# Shield.net
KiCad netlist of a schematic drawn in EAGLE
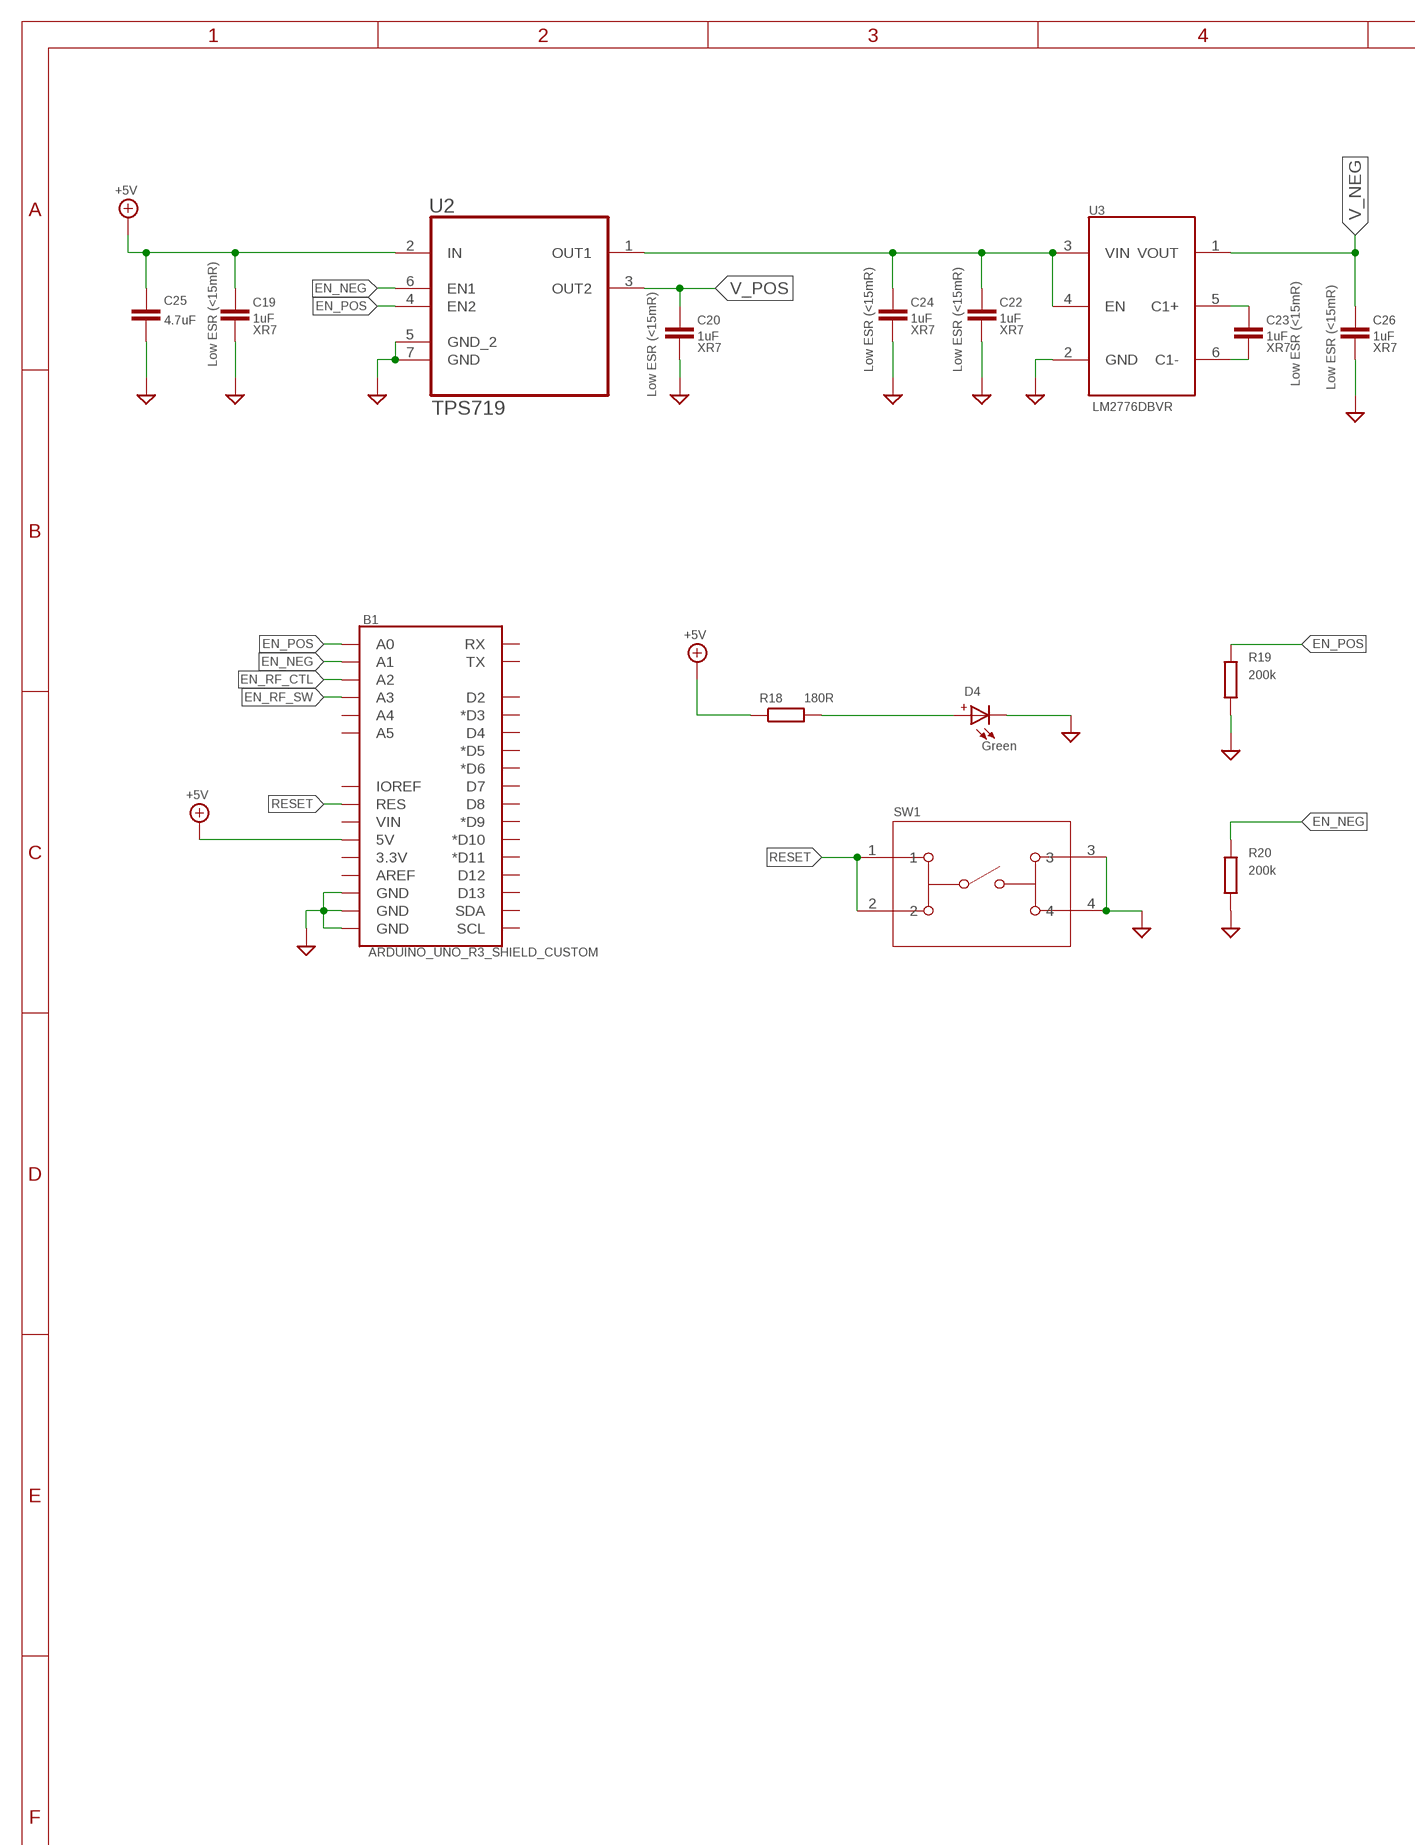
[diagram p0: schematic, sheet 1, part 1 of 2]
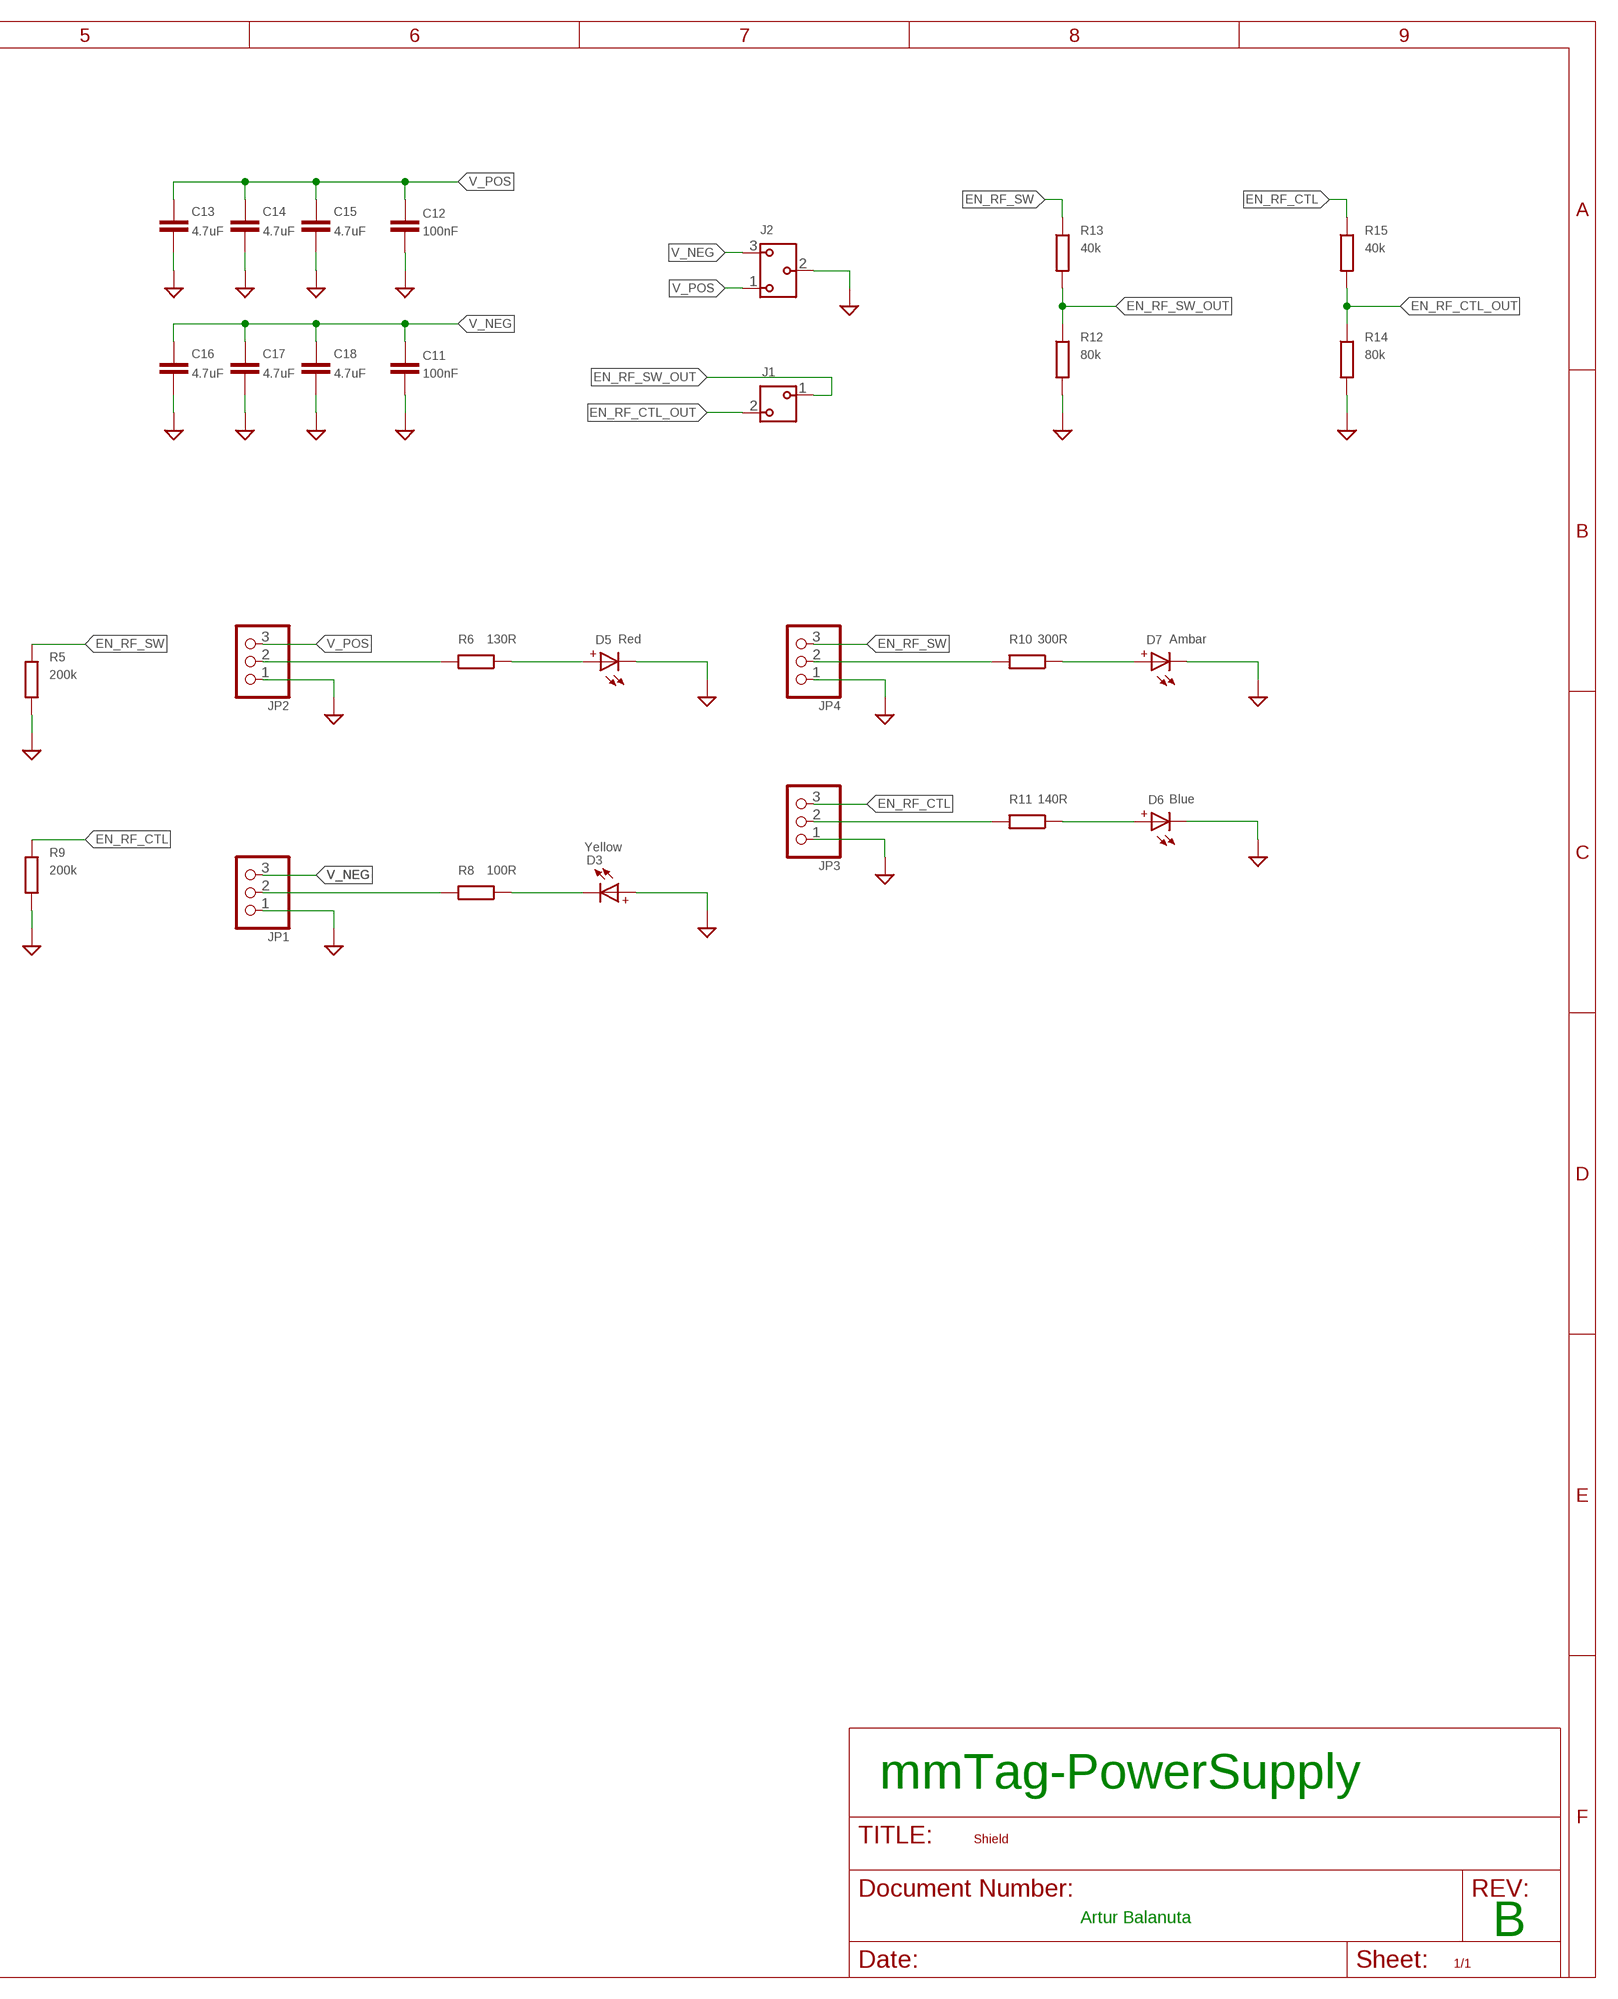
[diagram p1: schematic, sheet 1, part 2 of 2]

(export (version "E")
  (design (tool "Eeschema 10.0.6"))
  (components
    (comp (ref "B1")
      (value "ARDUINO_UNO_R3_SHIELD_CUSTOM")
      (footprint "eagle-import:UNO_R3_SHIELD_NO_PROG")
      (libsource (lib "eagle-import") (part "ARDUINO_UNO_R3_SHIELD_CUSTOM"))
    )
    (comp (ref "C11")
      (value "100nF")
      (footprint "eagle-import:C0603")
      (libsource (lib "eagle-import") (part "C-EUC0603"))
    )
    (comp (ref "C12")
      (value "100nF")
      (footprint "eagle-import:C0603")
      (libsource (lib "eagle-import") (part "C-EUC0603"))
    )
    (comp (ref "C13")
      (value "4.7uF")
      (footprint "eagle-import:C1206")
      (libsource (lib "eagle-import") (part "C-EUC1206"))
    )
    (comp (ref "C14")
      (value "4.7uF")
      (footprint "eagle-import:C1206")
      (libsource (lib "eagle-import") (part "C-EUC1206"))
    )
    (comp (ref "C15")
      (value "4.7uF")
      (footprint "eagle-import:C1206")
      (libsource (lib "eagle-import") (part "C-EUC1206"))
    )
    (comp (ref "C16")
      (value "4.7uF")
      (footprint "eagle-import:C1206")
      (libsource (lib "eagle-import") (part "C-EUC1206"))
    )
    (comp (ref "C17")
      (value "4.7uF")
      (footprint "eagle-import:C1206")
      (libsource (lib "eagle-import") (part "C-EUC1206"))
    )
    (comp (ref "C18")
      (value "4.7uF")
      (footprint "eagle-import:C1206")
      (libsource (lib "eagle-import") (part "C-EUC1206"))
    )
    (comp (ref "C19")
      (value "1uF")
      (footprint "eagle-import:C0603")
      (fields (field (name "ESR") "Low ESR (<15mR)") (field (name "TYPE") "XR7"))
      (libsource (lib "eagle-import") (part "C-EUC0603"))
    )
    (comp (ref "C20")
      (value "1uF")
      (footprint "eagle-import:C0603")
      (fields (field (name "ESR") "Low ESR (<15mR)") (field (name "TYPE") "XR7"))
      (libsource (lib "eagle-import") (part "C-EUC0603"))
    )
    (comp (ref "C22")
      (value "1uF")
      (footprint "eagle-import:C0603")
      (fields (field (name "ESR") "Low ESR (<15mR)") (field (name "TYPE") "XR7"))
      (libsource (lib "eagle-import") (part "C-EUC0603"))
    )
    (comp (ref "C23")
      (value "1uF")
      (footprint "eagle-import:C0603")
      (fields (field (name "ESR") "Low ESR (<15mR)") (field (name "TYPE") "XR7"))
      (libsource (lib "eagle-import") (part "C-EUC0603"))
    )
    (comp (ref "C24")
      (value "1uF")
      (footprint "eagle-import:C0603")
      (fields (field (name "ESR") "Low ESR (<15mR)") (field (name "TYPE") "XR7"))
      (libsource (lib "eagle-import") (part "C-EUC0603"))
    )
    (comp (ref "C25")
      (value "4.7uF")
      (footprint "eagle-import:C1206")
      (libsource (lib "eagle-import") (part "C-EUC1206"))
    )
    (comp (ref "C26")
      (value "1uF")
      (footprint "eagle-import:C0603")
      (fields (field (name "ESR") "Low ESR (<15mR)") (field (name "TYPE") "XR7"))
      (libsource (lib "eagle-import") (part "C-EUC0603"))
    )
    (comp (ref "D3")
      (value "WL-SMCW-150080YS75000")
      (footprint "eagle-import:WL-SMCW_0805")
      (fields (field (name "COLOR") "Yellow"))
      (libsource (lib "eagle-import") (part "WL-SMCW-150080YS75000"))
    )
    (comp (ref "D4")
      (value "WL-SMCW-150080GS75000")
      (footprint "eagle-import:WL-SMCW_0805")
      (fields (field (name "COLOR") "Green"))
      (libsource (lib "eagle-import") (part "WL-SMCW-150080GS75000"))
    )
    (comp (ref "D5")
      (value "WL-SMCW-150080RS75000")
      (footprint "eagle-import:WL-SMCW_0805")
      (fields (field (name "COLOR") "Red"))
      (libsource (lib "eagle-import") (part "WL-SMCW-150080RS75000"))
    )
    (comp (ref "D6")
      (value "WL-SMCW-150080BS75000")
      (footprint "eagle-import:WL-SMCW_0805")
      (fields (field (name "COLOR") "Blue"))
      (libsource (lib "eagle-import") (part "WL-SMCW-150080BS75000"))
    )
    (comp (ref "D7")
      (value "WL-SMCW_150080AS75000")
      (footprint "eagle-import:WL-SMCW_0805")
      (fields (field (name "COLOR") "Ambar"))
      (libsource (lib "eagle-import") (part "WL-SMCW_150080AS75000"))
    )
    (comp (ref "J1")
      (value "691412320002")
      (footprint "eagle-import:691412320002")
      (libsource (lib "eagle-import") (part "691412320002"))
    )
    (comp (ref "J2")
      (value "691412320003")
      (footprint "eagle-import:691412320003")
      (libsource (lib "eagle-import") (part "691412320003"))
    )
    (comp (ref "JP1")
      (value "PINHD-1X3")
      (footprint "eagle-import:1X03")
      (libsource (lib "eagle-import") (part "PINHD-1X3"))
    )
    (comp (ref "JP2")
      (value "PINHD-1X3")
      (footprint "eagle-import:1X03")
      (libsource (lib "eagle-import") (part "PINHD-1X3"))
    )
    (comp (ref "JP3")
      (value "PINHD-1X3")
      (footprint "eagle-import:1X03")
      (libsource (lib "eagle-import") (part "PINHD-1X3"))
    )
    (comp (ref "JP4")
      (value "PINHD-1X3")
      (footprint "eagle-import:1X03")
      (libsource (lib "eagle-import") (part "PINHD-1X3"))
    )
    (comp (ref "R5")
      (value "200k")
      (footprint "eagle-import:R0603")
      (libsource (lib "eagle-import") (part "R-EU_R0603"))
    )
    (comp (ref "R6")
      (value "130R")
      (footprint "eagle-import:R0603")
      (libsource (lib "eagle-import") (part "R-EU_R0603"))
    )
    (comp (ref "R8")
      (value "100R")
      (footprint "eagle-import:R0603")
      (libsource (lib "eagle-import") (part "R-EU_R0603"))
    )
    (comp (ref "R9")
      (value "200k")
      (footprint "eagle-import:R0603")
      (libsource (lib "eagle-import") (part "R-EU_R0603"))
    )
    (comp (ref "R10")
      (value "300R")
      (footprint "eagle-import:R0603")
      (libsource (lib "eagle-import") (part "R-EU_R0603"))
    )
    (comp (ref "R11")
      (value "140R")
      (footprint "eagle-import:R0603")
      (libsource (lib "eagle-import") (part "R-EU_R0603"))
    )
    (comp (ref "R12")
      (value "80k")
      (footprint "eagle-import:R0603")
      (libsource (lib "eagle-import") (part "R-EU_R0603"))
    )
    (comp (ref "R13")
      (value "40k")
      (footprint "eagle-import:R0603")
      (libsource (lib "eagle-import") (part "R-EU_R0603"))
    )
    (comp (ref "R14")
      (value "80k")
      (footprint "eagle-import:R0603")
      (libsource (lib "eagle-import") (part "R-EU_R0603"))
    )
    (comp (ref "R15")
      (value "40k")
      (footprint "eagle-import:R0603")
      (libsource (lib "eagle-import") (part "R-EU_R0603"))
    )
    (comp (ref "R18")
      (value "180R")
      (footprint "eagle-import:R0603")
      (libsource (lib "eagle-import") (part "R-EU_R0603"))
    )
    (comp (ref "R19")
      (value "200k")
      (footprint "eagle-import:R0603")
      (libsource (lib "eagle-import") (part "R-EU_R0603"))
    )
    (comp (ref "R20")
      (value "200k")
      (footprint "eagle-import:R0603")
      (libsource (lib "eagle-import") (part "R-EU_R0603"))
    )
    (comp (ref "SW1")
      (value "1825910-6")
      (footprint "eagle-import:SW4_1825910-B")
      (fields (field (name "COPYRIGHT") "Copyright (C) 2016 Accelerated Designs. All rights reserved"))
      (libsource (lib "eagle-import") (part "1825910-6"))
    )
    (comp (ref "U2")
      (value "TPS719")
      (footprint "eagle-import:SON6_5P200X200X80-7N")
      (fields (field (name "MF") "Texas Instruments"))
      (libsource (lib "eagle-import") (part "TPS719"))
    )
    (comp (ref "U3")
      (value "LM2776DBVR")
      (footprint "eagle-import:TEXAS_SOT23-6")
      (libsource (lib "eagle-import") (part "LM2776DBVR"))
    )
  )
  (nets
    (net (code "1") (name "+5V") (class "Default")
      (node (ref "B1") (pin "5V") (pinfunction "5V_5V") (pintype "bidirectional"))
      (node (ref "C19") (pin "1") (pinfunction "1_1") (pintype "passive"))
      (node (ref "C25") (pin "1") (pinfunction "1_1") (pintype "passive"))
      (node (ref "R18") (pin "1") (pinfunction "1_1") (pintype "passive"))
      (node (ref "U2") (pin "2") (pinfunction "IN_2") (pintype "power_in"))
    )
    (net (code "2") (name "EN_NEG") (class "Default")
      (node (ref "B1") (pin "A1") (pinfunction "A1_A1") (pintype "bidirectional"))
      (node (ref "R20") (pin "1") (pinfunction "1_1") (pintype "passive"))
      (node (ref "U2") (pin "6") (pinfunction "EN1_6") (pintype "input"))
    )
    (net (code "3") (name "EN_POS") (class "Default")
      (node (ref "B1") (pin "A0") (pinfunction "A0_A0") (pintype "bidirectional"))
      (node (ref "R19") (pin "1") (pinfunction "1_1") (pintype "passive"))
      (node (ref "U2") (pin "4") (pinfunction "EN2_4") (pintype "input"))
    )
    (net (code "4") (name "EN_RF_CTL") (class "Default")
      (node (ref "B1") (pin "A2") (pinfunction "A2_A2") (pintype "bidirectional"))
      (node (ref "JP3") (pin "3") (pinfunction "3_3") (pintype "passive"))
      (node (ref "R15") (pin "1") (pinfunction "1_1") (pintype "passive"))
      (node (ref "R9") (pin "1") (pinfunction "1_1") (pintype "passive"))
    )
    (net (code "5") (name "EN_RF_CTL_OUT") (class "Default")
      (node (ref "J1") (pin "2") (pinfunction "2_2") (pintype "passive"))
      (node (ref "R14") (pin "1") (pinfunction "1_1") (pintype "passive"))
      (node (ref "R15") (pin "2") (pinfunction "2_2") (pintype "passive"))
    )
    (net (code "6") (name "EN_RF_SW") (class "Default")
      (node (ref "B1") (pin "A3") (pinfunction "A3_A3") (pintype "bidirectional"))
      (node (ref "JP4") (pin "3") (pinfunction "3_3") (pintype "passive"))
      (node (ref "R13") (pin "1") (pinfunction "1_1") (pintype "passive"))
      (node (ref "R5") (pin "1") (pinfunction "1_1") (pintype "passive"))
    )
    (net (code "7") (name "EN_RF_SW_OUT") (class "Default")
      (node (ref "J1") (pin "1") (pinfunction "1_1") (pintype "passive"))
      (node (ref "R12") (pin "1") (pinfunction "1_1") (pintype "passive"))
      (node (ref "R13") (pin "2") (pinfunction "2_2") (pintype "passive"))
    )
    (net (code "8") (name "GND") (class "Default")
      (node (ref "B1") (pin "GND@0") (pinfunction "GND_GND@0") (pintype "bidirectional"))
      (node (ref "B1") (pin "GND@1") (pinfunction "GND_GND@1") (pintype "bidirectional"))
      (node (ref "B1") (pin "GND@2") (pinfunction "GND_GND@2") (pintype "bidirectional"))
      (node (ref "C11") (pin "2") (pinfunction "2_2") (pintype "passive"))
      (node (ref "C12") (pin "2") (pinfunction "2_2") (pintype "passive"))
      (node (ref "C13") (pin "2") (pinfunction "2_2") (pintype "passive"))
      (node (ref "C14") (pin "2") (pinfunction "2_2") (pintype "passive"))
      (node (ref "C15") (pin "2") (pinfunction "2_2") (pintype "passive"))
      (node (ref "C16") (pin "2") (pinfunction "2_2") (pintype "passive"))
      (node (ref "C17") (pin "2") (pinfunction "2_2") (pintype "passive"))
      (node (ref "C18") (pin "2") (pinfunction "2_2") (pintype "passive"))
      (node (ref "C19") (pin "2") (pinfunction "2_2") (pintype "passive"))
      (node (ref "C20") (pin "2") (pinfunction "2_2") (pintype "passive"))
      (node (ref "C22") (pin "2") (pinfunction "2_2") (pintype "passive"))
      (node (ref "C24") (pin "2") (pinfunction "2_2") (pintype "passive"))
      (node (ref "C25") (pin "2") (pinfunction "2_2") (pintype "passive"))
      (node (ref "C26") (pin "2") (pinfunction "2_2") (pintype "passive"))
      (node (ref "D3") (pin "2") (pinfunction "+_2") (pintype "passive"))
      (node (ref "D4") (pin "1") (pinfunction "-_1") (pintype "passive"))
      (node (ref "D5") (pin "1") (pinfunction "-_1") (pintype "passive"))
      (node (ref "D6") (pin "1") (pinfunction "-_1") (pintype "passive"))
      (node (ref "D7") (pin "1") (pinfunction "-_1") (pintype "passive"))
      (node (ref "J2") (pin "2") (pinfunction "2_2") (pintype "passive"))
      (node (ref "JP1") (pin "1") (pinfunction "1_1") (pintype "passive"))
      (node (ref "JP2") (pin "1") (pinfunction "1_1") (pintype "passive"))
      (node (ref "JP3") (pin "1") (pinfunction "1_1") (pintype "passive"))
      (node (ref "JP4") (pin "1") (pinfunction "1_1") (pintype "passive"))
      (node (ref "R12") (pin "2") (pinfunction "2_2") (pintype "passive"))
      (node (ref "R14") (pin "2") (pinfunction "2_2") (pintype "passive"))
      (node (ref "R19") (pin "2") (pinfunction "2_2") (pintype "passive"))
      (node (ref "R20") (pin "2") (pinfunction "2_2") (pintype "passive"))
      (node (ref "R5") (pin "2") (pinfunction "2_2") (pintype "passive"))
      (node (ref "R9") (pin "2") (pinfunction "2_2") (pintype "passive"))
      (node (ref "SW1") (pin "3") (pinfunction "3_3") (pintype "passive"))
      (node (ref "SW1") (pin "4") (pinfunction "4_4") (pintype "passive"))
      (node (ref "U2") (pin "5") (pinfunction "GND_2_5") (pintype "passive"))
      (node (ref "U2") (pin "7") (pinfunction "GND_7") (pintype "passive"))
      (node (ref "U3") (pin "2") (pinfunction "GND_2") (pintype "bidirectional"))
    )
    (net (code "9") (name "Net-(D3--)") (class "Default")
      (node (ref "D3") (pin "1") (pinfunction "-_1") (pintype "passive"))
      (node (ref "R8") (pin "1") (pinfunction "1_1") (pintype "passive"))
    )
    (net (code "10") (name "Net-(D4-+)") (class "Default")
      (node (ref "D4") (pin "2") (pinfunction "+_2") (pintype "passive"))
      (node (ref "R18") (pin "2") (pinfunction "2_2") (pintype "passive"))
    )
    (net (code "11") (name "Net-(D5-+)") (class "Default")
      (node (ref "D5") (pin "2") (pinfunction "+_2") (pintype "passive"))
      (node (ref "R6") (pin "1") (pinfunction "1_1") (pintype "passive"))
    )
    (net (code "12") (name "Net-(D6-+)") (class "Default")
      (node (ref "D6") (pin "2") (pinfunction "+_2") (pintype "passive"))
      (node (ref "R11") (pin "1") (pinfunction "1_1") (pintype "passive"))
    )
    (net (code "13") (name "Net-(D7-+)") (class "Default")
      (node (ref "D7") (pin "2") (pinfunction "+_2") (pintype "passive"))
      (node (ref "R10") (pin "1") (pinfunction "1_1") (pintype "passive"))
    )
    (net (code "14") (name "Net-(JP1-Pad2)") (class "Default")
      (node (ref "JP1") (pin "2") (pinfunction "2_2") (pintype "passive"))
      (node (ref "R8") (pin "2") (pinfunction "2_2") (pintype "passive"))
    )
    (net (code "15") (name "Net-(JP2-Pad2)") (class "Default")
      (node (ref "JP2") (pin "2") (pinfunction "2_2") (pintype "passive"))
      (node (ref "R6") (pin "2") (pinfunction "2_2") (pintype "passive"))
    )
    (net (code "16") (name "Net-(JP3-Pad2)") (class "Default")
      (node (ref "JP3") (pin "2") (pinfunction "2_2") (pintype "passive"))
      (node (ref "R11") (pin "2") (pinfunction "2_2") (pintype "passive"))
    )
    (net (code "17") (name "Net-(JP4-Pad2)") (class "Default")
      (node (ref "JP4") (pin "2") (pinfunction "2_2") (pintype "passive"))
      (node (ref "R10") (pin "2") (pinfunction "2_2") (pintype "passive"))
    )
    (net (code "18") (name "Net-(U2-OUT1)") (class "Default")
      (node (ref "C22") (pin "1") (pinfunction "1_1") (pintype "passive"))
      (node (ref "C24") (pin "1") (pinfunction "1_1") (pintype "passive"))
      (node (ref "U2") (pin "1") (pinfunction "OUT1_1") (pintype "output"))
      (node (ref "U3") (pin "3") (pinfunction "VIN_3") (pintype "bidirectional"))
      (node (ref "U3") (pin "4") (pinfunction "EN_4") (pintype "bidirectional"))
    )
    (net (code "19") (name "Net-(U3-C1+)") (class "Default")
      (node (ref "C23") (pin "1") (pinfunction "1_1") (pintype "passive"))
      (node (ref "U3") (pin "5") (pinfunction "C1+_5") (pintype "bidirectional"))
    )
    (net (code "20") (name "Net-(U3-C1-)") (class "Default")
      (node (ref "C23") (pin "2") (pinfunction "2_2") (pintype "passive"))
      (node (ref "U3") (pin "6") (pinfunction "C1-_6") (pintype "bidirectional"))
    )
    (net (code "21") (name "RESET") (class "Default")
      (node (ref "B1") (pin "RES") (pinfunction "RES_RES") (pintype "bidirectional"))
      (node (ref "SW1") (pin "1") (pinfunction "1_1") (pintype "passive"))
      (node (ref "SW1") (pin "2") (pinfunction "2_2") (pintype "passive"))
    )
    (net (code "22") (name "V_NEG") (class "Default")
      (node (ref "C11") (pin "1") (pinfunction "1_1") (pintype "passive"))
      (node (ref "C16") (pin "1") (pinfunction "1_1") (pintype "passive"))
      (node (ref "C17") (pin "1") (pinfunction "1_1") (pintype "passive"))
      (node (ref "C18") (pin "1") (pinfunction "1_1") (pintype "passive"))
      (node (ref "C26") (pin "1") (pinfunction "1_1") (pintype "passive"))
      (node (ref "J2") (pin "3") (pinfunction "3_3") (pintype "passive"))
      (node (ref "JP1") (pin "3") (pinfunction "3_3") (pintype "passive"))
      (node (ref "U3") (pin "1") (pinfunction "VOUT_1") (pintype "bidirectional"))
    )
    (net (code "23") (name "V_POS") (class "Default")
      (node (ref "C12") (pin "1") (pinfunction "1_1") (pintype "passive"))
      (node (ref "C13") (pin "1") (pinfunction "1_1") (pintype "passive"))
      (node (ref "C14") (pin "1") (pinfunction "1_1") (pintype "passive"))
      (node (ref "C15") (pin "1") (pinfunction "1_1") (pintype "passive"))
      (node (ref "C20") (pin "1") (pinfunction "1_1") (pintype "passive"))
      (node (ref "J2") (pin "1") (pinfunction "1_1") (pintype "passive"))
      (node (ref "JP2") (pin "3") (pinfunction "3_3") (pintype "passive"))
      (node (ref "U2") (pin "3") (pinfunction "OUT2_3") (pintype "output"))
    )
    (net (code "24") (name "unconnected-(B1-*D3-PadD3)") (class "Default")
      (node (ref "B1") (pin "D3") (pinfunction "*D3_D3") (pintype "bidirectional"))
    )
    (net (code "25") (name "unconnected-(B1-*D5-PadD5)") (class "Default")
      (node (ref "B1") (pin "D5") (pinfunction "*D5_D5") (pintype "bidirectional"))
    )
    (net (code "26") (name "unconnected-(B1-*D6-PadD6)") (class "Default")
      (node (ref "B1") (pin "D6") (pinfunction "*D6_D6") (pintype "bidirectional"))
    )
    (net (code "27") (name "unconnected-(B1-*D9-PadD9)") (class "Default")
      (node (ref "B1") (pin "D9") (pinfunction "*D9_D9") (pintype "bidirectional"))
    )
    (net (code "28") (name "unconnected-(B1-*D10-PadD10)") (class "Default")
      (node (ref "B1") (pin "D10") (pinfunction "*D10_D10") (pintype "bidirectional"))
    )
    (net (code "29") (name "unconnected-(B1-*D11-PadD11)") (class "Default")
      (node (ref "B1") (pin "D11") (pinfunction "*D11_D11") (pintype "bidirectional"))
    )
    (net (code "30") (name "unconnected-(B1-Pad3.3V)") (class "Default")
      (node (ref "B1") (pin "3.3V") (pinfunction "3.3V_3.3V") (pintype "bidirectional"))
    )
    (net (code "31") (name "unconnected-(B1-PadA4)") (class "Default")
      (node (ref "B1") (pin "A4") (pinfunction "A4_A4") (pintype "bidirectional"))
    )
    (net (code "32") (name "unconnected-(B1-PadA5)") (class "Default")
      (node (ref "B1") (pin "A5") (pinfunction "A5_A5") (pintype "bidirectional"))
    )
    (net (code "33") (name "unconnected-(B1-PadAREF)") (class "Default")
      (node (ref "B1") (pin "AREF") (pinfunction "AREF_AREF") (pintype "bidirectional"))
    )
    (net (code "34") (name "unconnected-(B1-PadD2)") (class "Default")
      (node (ref "B1") (pin "D2") (pinfunction "D2_D2") (pintype "bidirectional"))
    )
    (net (code "35") (name "unconnected-(B1-PadD4)") (class "Default")
      (node (ref "B1") (pin "D4") (pinfunction "D4_D4") (pintype "bidirectional"))
    )
    (net (code "36") (name "unconnected-(B1-PadD7)") (class "Default")
      (node (ref "B1") (pin "D7") (pinfunction "D7_D7") (pintype "bidirectional"))
    )
    (net (code "37") (name "unconnected-(B1-PadD8)") (class "Default")
      (node (ref "B1") (pin "D8") (pinfunction "D8_D8") (pintype "bidirectional"))
    )
    (net (code "38") (name "unconnected-(B1-PadD12)") (class "Default")
      (node (ref "B1") (pin "D12") (pinfunction "D12_D12") (pintype "bidirectional"))
    )
    (net (code "39") (name "unconnected-(B1-PadD13)") (class "Default")
      (node (ref "B1") (pin "D13") (pinfunction "D13_D13") (pintype "bidirectional"))
    )
    (net (code "40") (name "unconnected-(B1-PadIOREF)") (class "Default")
      (node (ref "B1") (pin "IOREF") (pinfunction "IOREF_IOREF") (pintype "bidirectional"))
    )
    (net (code "41") (name "unconnected-(B1-PadRX)") (class "Default")
      (node (ref "B1") (pin "RX") (pinfunction "RX_RX") (pintype "bidirectional"))
    )
    (net (code "42") (name "unconnected-(B1-PadSCL)") (class "Default")
      (node (ref "B1") (pin "SCL") (pinfunction "SCL_SCL") (pintype "bidirectional"))
    )
    (net (code "43") (name "unconnected-(B1-PadSDA)") (class "Default")
      (node (ref "B1") (pin "SDA") (pinfunction "SDA_SDA") (pintype "bidirectional"))
    )
    (net (code "44") (name "unconnected-(B1-PadTX)") (class "Default")
      (node (ref "B1") (pin "TX") (pinfunction "TX_TX") (pintype "bidirectional"))
    )
    (net (code "45") (name "unconnected-(B1-PadVIN)") (class "Default")
      (node (ref "B1") (pin "VIN") (pinfunction "VIN_VIN") (pintype "bidirectional"))
    )
  )
)
